# Redriver.net
KiCad netlist of a schematic drawn in Altium Designer
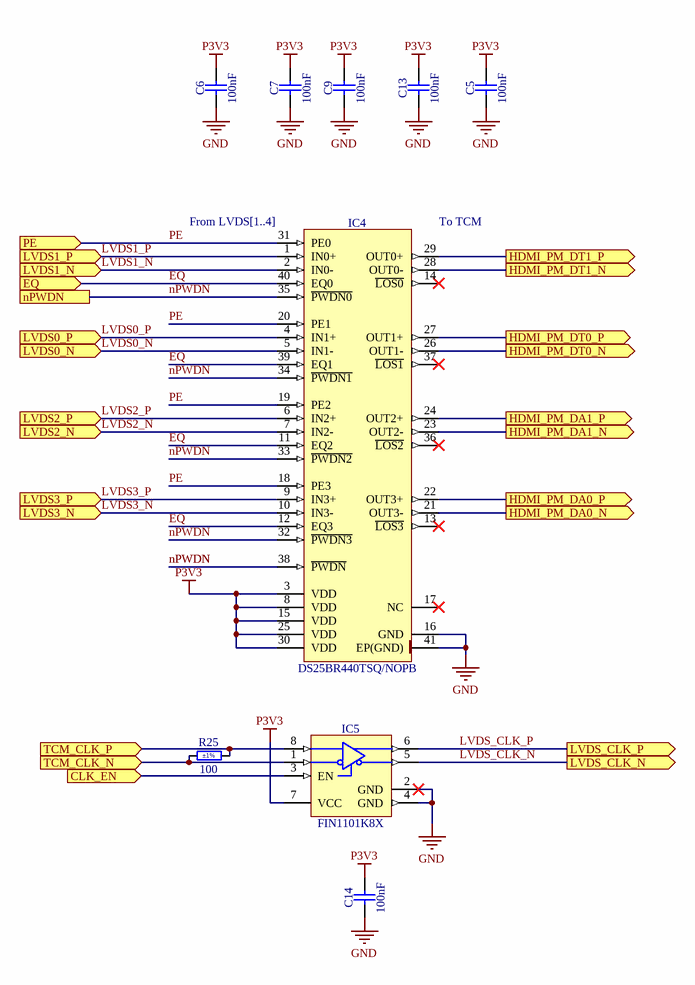
[diagram p0: Redriver.SchDoc]

(export (version "E")
  (design (tool "Eeschema 10.0.6"))
  (components
    (comp (ref "C5")
      (value "100nF")
      (footprint "CAPC1005X55N")
      (description "Non-polarised capacitor")
      (fields
        (field (name "PART NUMBER") "CC0402_100NF_50V_10%_X7R")
        (field (name "VOLTAGE") "50V")
        (field (name "AUTHOR") "CERN DEM MR")
      )
      (libsource (lib "Capacitors") (part "Capacitor - non polarized"))
    )
    (comp (ref "C6")
      (value "100nF")
      (footprint "CAPC1005X55N")
      (description "Non-polarised capacitor")
      (fields
        (field (name "PART NUMBER") "CC0402_100NF_50V_10%_X7R")
        (field (name "VOLTAGE") "50V")
        (field (name "AUTHOR") "CERN DEM MR")
      )
      (libsource (lib "Capacitors") (part "Capacitor - non polarized"))
    )
    (comp (ref "C7")
      (value "100nF")
      (footprint "CAPC1005X55N")
      (description "Non-polarised capacitor")
      (fields
        (field (name "PART NUMBER") "CC0402_100NF_50V_10%_X7R")
        (field (name "VOLTAGE") "50V")
        (field (name "AUTHOR") "CERN DEM MR")
      )
      (libsource (lib "Capacitors") (part "Capacitor - non polarized"))
    )
    (comp (ref "C9")
      (value "100nF")
      (footprint "CAPC1005X55N")
      (description "Non-polarised capacitor")
      (fields
        (field (name "PART NUMBER") "CC0402_100NF_50V_10%_X7R")
        (field (name "VOLTAGE") "50V")
        (field (name "AUTHOR") "CERN DEM MR")
      )
      (libsource (lib "Capacitors") (part "Capacitor - non polarized"))
    )
    (comp (ref "C13")
      (value "100nF")
      (footprint "CAPC1005X55N")
      (description "Non-polarised capacitor")
      (fields
        (field (name "PART NUMBER") "CC0402_100NF_50V_10%_X7R")
        (field (name "VOLTAGE") "50V")
        (field (name "AUTHOR") "CERN DEM MR")
      )
      (libsource (lib "Capacitors") (part "Capacitor - non polarized"))
    )
    (comp (ref "C14")
      (value "100nF")
      (footprint "CAPC1005X55N")
      (description "Non-polarised capacitor")
      (fields
        (field (name "PART NUMBER") "CC0402_100NF_50V_10%_X7R")
        (field (name "VOLTAGE") "50V")
        (field (name "AUTHOR") "CERN DEM MR")
      )
      (libsource (lib "Capacitors") (part "Capacitor - non polarized"))
    )
    (comp (ref "IC4")
      (value "DS25BR440TSQ/NOPB")
      (footprint "QFN50P600X600X80-41N-S480")
      (description "3.125-Gbps Quad LVDS Buffer with Transmit Pre-Emphasis and Receive Equalization")
      (fields
        (field (name "MANUFACTURER") "TEXAS INSTRUMENTS")
        (field (name "MANUFACTURER PART NUMBER") "DS25BR440TSQ")
        (field (name "AUTHOR") "CERN DEM HF")
      )
      (libsource (lib "ICs And Semiconductors") (part "DS25BR440"))
    )
    (comp (ref "IC5")
      (value "FIN1101K8X")
      (footprint "SOP50P310X90-8N")
      (description "LVDS Single Port High Speed Repeater")
      (fields (field (name "MANUFACTURER") "FAIRCHILD SEMICONDUCTOR") (field (name "AUTHOR") "CERN DEM JLC"))
      (libsource (lib "ICs And Semiconductors") (part "FIN1101K8X"))
    )
    (comp (ref "R25")
      (value "100")
      (footprint "RESC1005X40N")
      (description "Resistor - 1%")
      (fields
        (field (name "TOLERANCE") "±1%")
        (field (name "PART NUMBER") "R0402_100R_1%_0.0625W_100PPM")
        (field (name "POWER") "0.0625W")
        (field (name "AUTHOR") "CERN DEM JLC")
      )
      (libsource (lib "Resistors") (part "Resistor - 1%"))
    )
  )
  (nets
    (net (code "1") (name "/CLK_EN") (class "Default")
      (node (ref "IC5") (pin "3") (pinfunction "EN_3") (pintype "input"))
    )
    (net (code "2") (name "/EQ") (class "Default")
      (node (ref "IC4") (pin "11") (pinfunction "EQ2_11") (pintype "input"))
      (node (ref "IC4") (pin "12") (pinfunction "EQ3_12") (pintype "input"))
      (node (ref "IC4") (pin "39") (pinfunction "EQ1_39") (pintype "input"))
      (node (ref "IC4") (pin "40") (pinfunction "EQ0_40") (pintype "input"))
    )
    (net (code "3") (name "/HDMI_PM_DA0_N") (class "Default")
      (node (ref "IC4") (pin "21") (pinfunction "OUT3-_21") (pintype "output"))
    )
    (net (code "4") (name "/HDMI_PM_DA0_P") (class "Default")
      (node (ref "IC4") (pin "22") (pinfunction "OUT3+_22") (pintype "output"))
    )
    (net (code "5") (name "/HDMI_PM_DA1_N") (class "Default")
      (node (ref "IC4") (pin "23") (pinfunction "OUT2-_23") (pintype "output"))
    )
    (net (code "6") (name "/HDMI_PM_DA1_P") (class "Default")
      (node (ref "IC4") (pin "24") (pinfunction "OUT2+_24") (pintype "output"))
    )
    (net (code "7") (name "/HDMI_PM_DT0_N") (class "Default")
      (node (ref "IC4") (pin "26") (pinfunction "OUT1-_26") (pintype "output"))
    )
    (net (code "8") (name "/HDMI_PM_DT0_P") (class "Default")
      (node (ref "IC4") (pin "27") (pinfunction "OUT1+_27") (pintype "output"))
    )
    (net (code "9") (name "/HDMI_PM_DT1_N") (class "Default")
      (node (ref "IC4") (pin "28") (pinfunction "OUT0-_28") (pintype "output"))
    )
    (net (code "10") (name "/HDMI_PM_DT1_P") (class "Default")
      (node (ref "IC4") (pin "29") (pinfunction "OUT0+_29") (pintype "output"))
    )
    (net (code "11") (name "/LVDS0_N") (class "Default")
      (node (ref "IC4") (pin "5") (pinfunction "IN1-_5") (pintype "input"))
    )
    (net (code "12") (name "/LVDS0_P") (class "Default")
      (node (ref "IC4") (pin "4") (pinfunction "IN1+_4") (pintype "input"))
    )
    (net (code "13") (name "/LVDS1_N") (class "Default")
      (node (ref "IC4") (pin "2") (pinfunction "IN0-_2") (pintype "input"))
    )
    (net (code "14") (name "/LVDS1_P") (class "Default")
      (node (ref "IC4") (pin "1") (pinfunction "IN0+_1") (pintype "input"))
    )
    (net (code "15") (name "/LVDS2_N") (class "Default")
      (node (ref "IC4") (pin "7") (pinfunction "IN2-_7") (pintype "input"))
    )
    (net (code "16") (name "/LVDS2_P") (class "Default")
      (node (ref "IC4") (pin "6") (pinfunction "IN2+_6") (pintype "input"))
    )
    (net (code "17") (name "/LVDS3_N") (class "Default")
      (node (ref "IC4") (pin "10") (pinfunction "IN3-_10") (pintype "input"))
    )
    (net (code "18") (name "/LVDS3_P") (class "Default")
      (node (ref "IC4") (pin "9") (pinfunction "IN3+_9") (pintype "input"))
    )
    (net (code "19") (name "/LVDS_CLK_N") (class "Default")
      (node (ref "IC5") (pin "5") (pinfunction "DOUT-_5") (pintype "output"))
    )
    (net (code "20") (name "/LVDS_CLK_P") (class "Default")
      (node (ref "IC5") (pin "6") (pinfunction "DOUT+_6") (pintype "output"))
    )
    (net (code "21") (name "/PE") (class "Default")
      (node (ref "IC4") (pin "18") (pinfunction "PE3_18") (pintype "input"))
      (node (ref "IC4") (pin "19") (pinfunction "PE2_19") (pintype "input"))
      (node (ref "IC4") (pin "20") (pinfunction "PE1_20") (pintype "input"))
      (node (ref "IC4") (pin "31") (pinfunction "PE0_31") (pintype "input"))
    )
    (net (code "22") (name "/TCM_CLK_N") (class "Default")
      (node (ref "IC5") (pin "1") (pinfunction "RIN-_1") (pintype "input"))
      (node (ref "R25") (pin "1") (pinfunction "1_1") (pintype "passive"))
    )
    (net (code "23") (name "/TCM_CLK_P") (class "Default")
      (node (ref "IC5") (pin "8") (pinfunction "RIN+_8") (pintype "input"))
      (node (ref "R25") (pin "2") (pinfunction "2_2") (pintype "passive"))
    )
    (net (code "24") (name "/nPWDN") (class "Default")
      (node (ref "IC4") (pin "32") (pinfunction "~{PWDN3}_32") (pintype "input"))
      (node (ref "IC4") (pin "33") (pinfunction "~{PWDN2}_33") (pintype "input"))
      (node (ref "IC4") (pin "34") (pinfunction "~{PWDN1}_34") (pintype "input"))
      (node (ref "IC4") (pin "35") (pinfunction "~{PWDN0}_35") (pintype "input"))
      (node (ref "IC4") (pin "38") (pinfunction "~{PWDN}_38") (pintype "input"))
    )
    (net (code "25") (name "GND") (class "Default")
      (node (ref "C13") (pin "1") (pinfunction "1_1") (pintype "passive"))
      (node (ref "C14") (pin "1") (pinfunction "1_1") (pintype "passive"))
      (node (ref "C5") (pin "1") (pinfunction "1_1") (pintype "passive"))
      (node (ref "C6") (pin "1") (pinfunction "1_1") (pintype "passive"))
      (node (ref "C7") (pin "1") (pinfunction "1_1") (pintype "passive"))
      (node (ref "C9") (pin "1") (pinfunction "1_1") (pintype "passive"))
      (node (ref "IC4") (pin "16") (pinfunction "GND_16") (pintype "power_in"))
      (node (ref "IC4") (pin "41") (pinfunction "EP(GND)_41") (pintype "power_in"))
      (node (ref "IC5") (pin "2") (pinfunction "GND_2") (pintype "power_in"))
      (node (ref "IC5") (pin "4") (pinfunction "GND_4") (pintype "output"))
    )
    (net (code "26") (name "P3V3") (class "Default")
      (node (ref "C13") (pin "2") (pinfunction "2_2") (pintype "passive"))
      (node (ref "C14") (pin "2") (pinfunction "2_2") (pintype "passive"))
      (node (ref "C5") (pin "2") (pinfunction "2_2") (pintype "passive"))
      (node (ref "C6") (pin "2") (pinfunction "2_2") (pintype "passive"))
      (node (ref "C7") (pin "2") (pinfunction "2_2") (pintype "passive"))
      (node (ref "C9") (pin "2") (pinfunction "2_2") (pintype "passive"))
      (node (ref "IC4") (pin "15") (pinfunction "VDD_15") (pintype "power_in"))
      (node (ref "IC4") (pin "25") (pinfunction "VDD_25") (pintype "power_in"))
      (node (ref "IC4") (pin "3") (pinfunction "VDD_3") (pintype "power_in"))
      (node (ref "IC4") (pin "30") (pinfunction "VDD_30") (pintype "power_in"))
      (node (ref "IC4") (pin "8") (pinfunction "VDD_8") (pintype "power_in"))
      (node (ref "IC5") (pin "7") (pinfunction "VCC_7") (pintype "power_in"))
    )
    (net (code "27") (name "unconnected-(IC4-NC-Pad17)") (class "Default")
      (node (ref "IC4") (pin "17") (pinfunction "NC_17") (pintype "passive+no_connect"))
    )
    (net (code "28") (name "unconnected-(IC4-~{LOS0}-Pad14)") (class "Default")
      (node (ref "IC4") (pin "14") (pinfunction "~{LOS0}_14") (pintype "output+no_connect"))
    )
    (net (code "29") (name "unconnected-(IC4-~{LOS1}-Pad37)") (class "Default")
      (node (ref "IC4") (pin "37") (pinfunction "~{LOS1}_37") (pintype "output+no_connect"))
    )
    (net (code "30") (name "unconnected-(IC4-~{LOS2}-Pad36)") (class "Default")
      (node (ref "IC4") (pin "36") (pinfunction "~{LOS2}_36") (pintype "output+no_connect"))
    )
    (net (code "31") (name "unconnected-(IC4-~{LOS3}-Pad13)") (class "Default")
      (node (ref "IC4") (pin "13") (pinfunction "~{LOS3}_13") (pintype "output+no_connect"))
    )
  )
)
